# Sheet1.net
KiCad netlist of a schematic drawn in Altium Designer
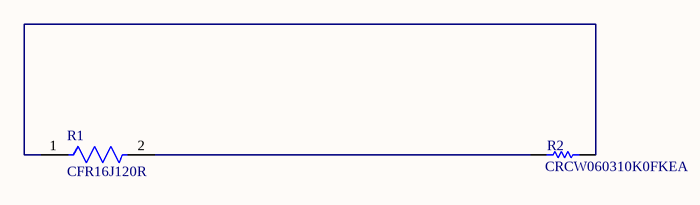
[diagram p0: Sheet1.SchDoc]

(export (version "E")
  (design (tool "Eeschema 10.0.6"))
  (components
    (comp (ref "R1")
      (value "CFR16J120R")
      (footprint "FP-CFR16-MFG")
      (description "RES 120 OHM 1/4W 5% AXIAL")
      (fields (field (name "TOLERANCE") "5%"))
      (libsource (lib "Altium Content Vault") (part "1029c3af85768c4190bb7ad29bc67b5"))
    )
    (comp (ref "R2")
      (value "CRCW060310K0FKEA")
      (footprint "RESC1609X50X30NL8T20")
      (description "Chip Resistor, 10 KOhm, +/- 1%, 100 mW, -55 to 155 degC, 0603 (1608 Metric), RoHS, Tape and Reel")
      (fields (field (name "MANUFACTURER") "Vishay Semiconductor"))
      (libsource (lib "Altium Content Vault") (part "RES-2"))
    )
  )
  (nets
    (net (code "1") (name "Net-(R1-Pad1)") (class "Default")
      (node (ref "R1") (pin "1") (pinfunction "1_1") (pintype "passive"))
      (node (ref "R2") (pin "2") (pinfunction "2_2") (pintype "passive"))
    )
    (net (code "2") (name "Net-(R1-Pad2)") (class "Default")
      (node (ref "R1") (pin "2") (pinfunction "2_2") (pintype "passive"))
      (node (ref "R2") (pin "1") (pinfunction "1_1") (pintype "passive"))
    )
  )
)
